# rs232_usart.net
KiCad netlist of a schematic drawn in Altium Designer
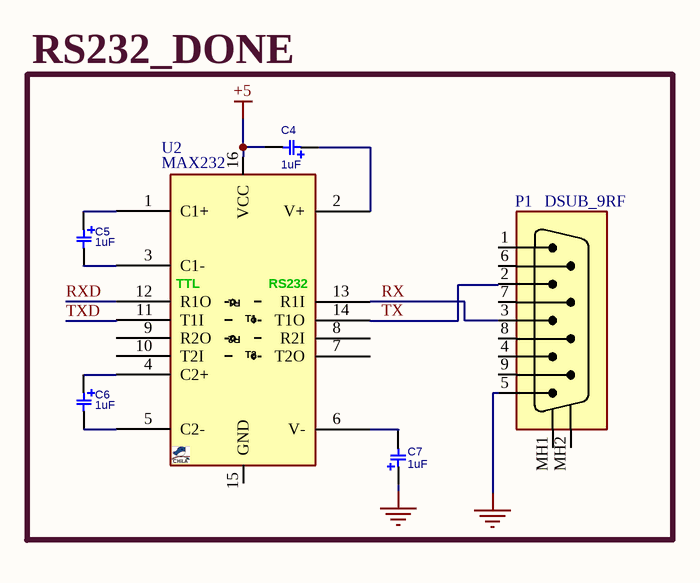
[diagram p0: rs232_usart.SchDoc]

(export (version "E")
  (design (tool "Eeschema 10.0.6"))
  (components
    (comp (ref "C4")
      (value "1uF")
      (footprint "C_EL_4X7")
      (description "CAP, THD, ELEC, 10uF, 25V")
      (fields (field (name "MANF") "MANF") (field (name "MANF_P#") "MANF_PART#"))
      (libsource (lib "CapElect_passive") (part "CAP_THD_EL_10u25V"))
    )
    (comp (ref "C5")
      (value "1uF")
      (footprint "C_EL_4X7")
      (description "CAP, THD, ELEC, 10uF, 25V")
      (fields (field (name "MANF") "MANF") (field (name "MANF_P#") "MANF_PART#"))
      (libsource (lib "CapElect_passive") (part "CAP_THD_EL_10u25V"))
    )
    (comp (ref "C6")
      (value "1uF")
      (footprint "C_EL_4X7")
      (description "CAP, THD, ELEC, 10uF, 25V")
      (fields (field (name "MANF") "MANF") (field (name "MANF_P#") "MANF_PART#"))
      (libsource (lib "CapElect_passive") (part "CAP_THD_EL_10u25V"))
    )
    (comp (ref "C7")
      (value "1uF")
      (footprint "C_EL_4X7")
      (description "CAP, THD, ELEC, 10uF, 25V")
      (fields (field (name "MANF") "MANF") (field (name "MANF_P#") "MANF_PART#"))
      (libsource (lib "CapElect_passive") (part "CAP_THD_EL_10u25V"))
    )
    (comp (ref "P1")
      (value "DSUB_9RF")
      (footprint "DSUB_9RF")
      (description "CONN, DSUB, HD, 9PIN, R/A, FEMALE, THD")
      (libsource (lib "conn_dsub") (part "CONN_DSUB_9RF"))
    )
    (comp (ref "U2")
      (value "MAX232")
      (footprint "DIP_16")
      (description "RS-232, DUAL, +5V, Driver/Receiver")
      (fields
        (field (name "MANF") "Texas Instruments, Maxim Integrated")
        (field (name "MANF_PART#") "MAX232N, MAX232ACPE")
      )
      (libsource (lib "rs232") (part "MAX232_DIP16"))
    )
  )
  (nets
    (net (code "1") (name "+5") (class "Default")
      (node (ref "C4") (pin "2") (pinfunction "2_2") (pintype "passive"))
      (node (ref "U2") (pin "16") (pinfunction "VCC_16") (pintype "power_in"))
    )
    (net (code "2") (name "/RX") (class "Default")
      (node (ref "P1") (pin "3") (pinfunction "3_3") (pintype "passive"))
      (node (ref "U2") (pin "13") (pinfunction "R1I_13") (pintype "passive"))
    )
    (net (code "3") (name "/RXD") (class "Default")
      (node (ref "U2") (pin "12") (pinfunction "R1O_12") (pintype "passive"))
    )
    (net (code "4") (name "/TX") (class "Default")
      (node (ref "P1") (pin "2") (pinfunction "2_2") (pintype "passive"))
      (node (ref "U2") (pin "14") (pinfunction "T1O_14") (pintype "passive"))
    )
    (net (code "5") (name "/TXD") (class "Default")
      (node (ref "U2") (pin "11") (pinfunction "T1I_11") (pintype "passive"))
    )
    (net (code "6") (name "GND") (class "Default")
      (node (ref "C7") (pin "1") (pinfunction "1_1") (pintype "passive"))
      (node (ref "P1") (pin "5") (pinfunction "5_5") (pintype "passive"))
    )
    (net (code "7") (name "Net-(U2-C1+)") (class "Default")
      (node (ref "C5") (pin "1") (pinfunction "1_1") (pintype "passive"))
      (node (ref "U2") (pin "1") (pinfunction "C1+_1") (pintype "passive"))
    )
    (net (code "8") (name "Net-(U2-C1-)") (class "Default")
      (node (ref "C5") (pin "2") (pinfunction "2_2") (pintype "passive"))
      (node (ref "U2") (pin "3") (pinfunction "C1-_3") (pintype "passive"))
    )
    (net (code "9") (name "Net-(U2-C2+)") (class "Default")
      (node (ref "C6") (pin "1") (pinfunction "1_1") (pintype "passive"))
      (node (ref "U2") (pin "4") (pinfunction "C2+_4") (pintype "passive"))
    )
    (net (code "10") (name "Net-(U2-C2-)") (class "Default")
      (node (ref "C6") (pin "2") (pinfunction "2_2") (pintype "passive"))
      (node (ref "U2") (pin "5") (pinfunction "C2-_5") (pintype "passive"))
    )
    (net (code "11") (name "Net-(U2-V+)") (class "Default")
      (node (ref "C4") (pin "1") (pinfunction "1_1") (pintype "passive"))
      (node (ref "U2") (pin "2") (pinfunction "V+_2") (pintype "passive"))
    )
    (net (code "12") (name "Net-(U2-V-)") (class "Default")
      (node (ref "C7") (pin "2") (pinfunction "2_2") (pintype "passive"))
      (node (ref "U2") (pin "6") (pinfunction "V-_6") (pintype "passive"))
    )
    (net (code "13") (name "unconnected-(P1-Pad1)") (class "Default")
      (node (ref "P1") (pin "1") (pinfunction "1_1") (pintype "passive"))
    )
    (net (code "14") (name "unconnected-(P1-Pad4)") (class "Default")
      (node (ref "P1") (pin "4") (pinfunction "4_4") (pintype "passive"))
    )
    (net (code "15") (name "unconnected-(P1-Pad6)") (class "Default")
      (node (ref "P1") (pin "6") (pinfunction "6_6") (pintype "passive"))
    )
    (net (code "16") (name "unconnected-(P1-Pad7)") (class "Default")
      (node (ref "P1") (pin "7") (pinfunction "7_7") (pintype "passive"))
    )
    (net (code "17") (name "unconnected-(P1-Pad8)") (class "Default")
      (node (ref "P1") (pin "8") (pinfunction "8_8") (pintype "passive"))
    )
    (net (code "18") (name "unconnected-(P1-Pad9)") (class "Default")
      (node (ref "P1") (pin "9") (pinfunction "9_9") (pintype "passive"))
    )
    (net (code "19") (name "unconnected-(P1-PadMH1)") (class "Default")
      (node (ref "P1") (pin "MH1") (pinfunction "MH1_MH1") (pintype "passive"))
    )
    (net (code "20") (name "unconnected-(P1-PadMH2)") (class "Default")
      (node (ref "P1") (pin "MH2") (pinfunction "MH2_MH2") (pintype "passive"))
    )
    (net (code "21") (name "unconnected-(U2-GND-Pad15)") (class "Default")
      (node (ref "U2") (pin "15") (pinfunction "GND_15") (pintype "power_in"))
    )
    (net (code "22") (name "unconnected-(U2-R2I-Pad8)") (class "Default")
      (node (ref "U2") (pin "8") (pinfunction "R2I_8") (pintype "passive"))
    )
    (net (code "23") (name "unconnected-(U2-R2O-Pad9)") (class "Default")
      (node (ref "U2") (pin "9") (pinfunction "R2O_9") (pintype "passive"))
    )
    (net (code "24") (name "unconnected-(U2-T2I-Pad10)") (class "Default")
      (node (ref "U2") (pin "10") (pinfunction "T2I_10") (pintype "passive"))
    )
    (net (code "25") (name "unconnected-(U2-T2O-Pad7)") (class "Default")
      (node (ref "U2") (pin "7") (pinfunction "T2O_7") (pintype "passive"))
    )
  )
)
